# SumoDuino.net
KiCad netlist of a schematic drawn in EAGLE
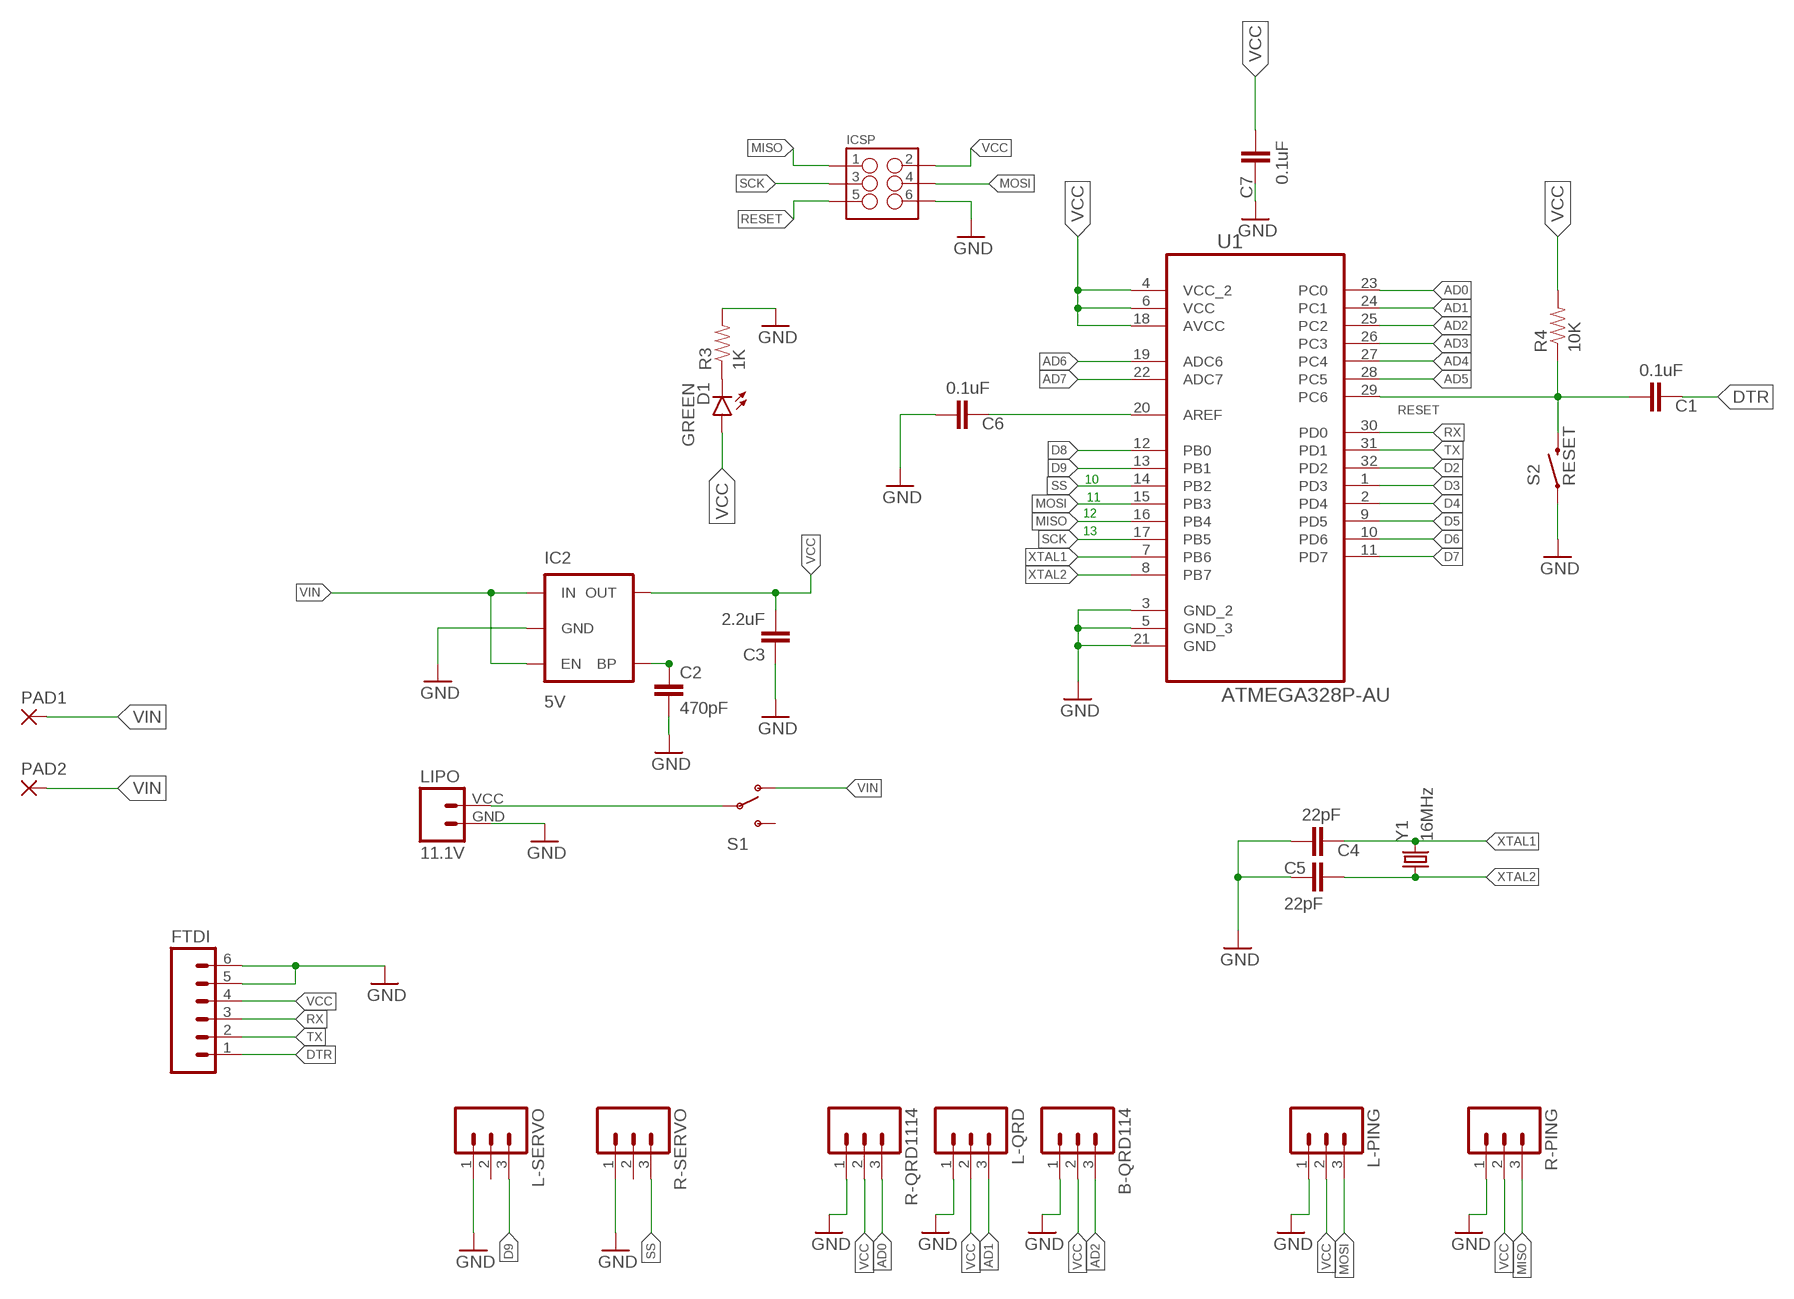
[diagram p0: schematic, sheet 1]

(export (version "E")
  (design (tool "Eeschema 10.0.6"))
  (components
    (comp (ref "B-QRD114")
      (value "M03PTH")
      (footprint "eagle-import:1X03")
      (libsource (lib "eagle-import") (part "M03PTH"))
    )
    (comp (ref "C1")
      (value "0.1uF")
      (footprint "eagle-import:0603-CAP")
      (libsource (lib "eagle-import") (part "CAP0603-CAP"))
    )
    (comp (ref "C2")
      (value "470pF")
      (footprint "eagle-import:0603-CAP")
      (libsource (lib "eagle-import") (part "CAP0603-CAP"))
    )
    (comp (ref "C3")
      (value "2.2uF")
      (footprint "eagle-import:0603-CAP")
      (libsource (lib "eagle-import") (part "CAP0603-CAP"))
    )
    (comp (ref "C4")
      (value "22pF")
      (footprint "eagle-import:0603-CAP")
      (libsource (lib "eagle-import") (part "CAP0603-CAP"))
    )
    (comp (ref "C5")
      (value "22pF")
      (footprint "eagle-import:0603-CAP")
      (libsource (lib "eagle-import") (part "CAP0603-CAP"))
    )
    (comp (ref "C6")
      (value "0.1uF")
      (footprint "eagle-import:0603-CAP")
      (libsource (lib "eagle-import") (part "CAP0603-CAP"))
    )
    (comp (ref "C7")
      (value "0.1uF")
      (footprint "eagle-import:0603-CAP")
      (libsource (lib "eagle-import") (part "CAP0603-CAP"))
    )
    (comp (ref "D1")
      (value "GREEN")
      (footprint "eagle-import:LED-0603")
      (libsource (lib "eagle-import") (part "LED-GREEN0603"))
    )
    (comp (ref "FTDI")
      (value "M06LOCK")
      (footprint "eagle-import:1X06_LOCK")
      (libsource (lib "eagle-import") (part "M06LOCK"))
    )
    (comp (ref "IC2")
      (value "5V")
      (footprint "eagle-import:SOT23-5")
      (libsource (lib "eagle-import") (part "V_REG_MIC52055V"))
    )
    (comp (ref "ICSP")
      (value "M03X22X3_SILK_MALE_PTH")
      (footprint "eagle-import:2X3")
      (libsource (lib "eagle-import") (part "M03X22X3_SILK_MALE_PTH"))
    )
    (comp (ref "L-PING")
      (value "M03PTH")
      (footprint "eagle-import:1X03")
      (libsource (lib "eagle-import") (part "M03PTH"))
    )
    (comp (ref "L-QRD")
      (value "M03PTH")
      (footprint "eagle-import:1X03")
      (libsource (lib "eagle-import") (part "M03PTH"))
    )
    (comp (ref "L-SERVO")
      (value "M03PTH")
      (footprint "eagle-import:1X03")
      (libsource (lib "eagle-import") (part "M03PTH"))
    )
    (comp (ref "LIPO")
      (value "11.1V")
      (footprint "eagle-import:JST-2-SMD-VERT")
      (libsource (lib "eagle-import") (part "M024UCON-15767"))
    )
    (comp (ref "PAD1")
      (value "1,6/0,8")
      (footprint "eagle-import:1,6_0,8")
      (libsource (lib "eagle-import") (part "1,6/0,8"))
    )
    (comp (ref "PAD2")
      (value "1,6/0,8")
      (footprint "eagle-import:1,6_0,8")
      (libsource (lib "eagle-import") (part "1,6/0,8"))
    )
    (comp (ref "R-PING")
      (value "M03PTH")
      (footprint "eagle-import:1X03")
      (libsource (lib "eagle-import") (part "M03PTH"))
    )
    (comp (ref "R-QRD1114")
      (value "M03PTH")
      (footprint "eagle-import:1X03")
      (libsource (lib "eagle-import") (part "M03PTH"))
    )
    (comp (ref "R-SERVO")
      (value "M03PTH")
      (footprint "eagle-import:1X03")
      (libsource (lib "eagle-import") (part "M03PTH"))
    )
    (comp (ref "R3")
      (value "1K")
      (footprint "eagle-import:0603-RES")
      (libsource (lib "eagle-import") (part "RESISTOR0603"))
    )
    (comp (ref "R4")
      (value "10K")
      (footprint "eagle-import:0603-RES")
      (libsource (lib "eagle-import") (part "RESISTOR0603"))
    )
    (comp (ref "S1")
      (value "SWITCH-SPDTPTH")
      (footprint "eagle-import:SWITCH-SPDT")
      (libsource (lib "eagle-import") (part "SWITCH-SPDTPTH"))
    )
    (comp (ref "S2")
      (value "RESET")
      (footprint "eagle-import:TACTILE-PTH")
      (libsource (lib "eagle-import") (part "SWITCH-MOMENTARY-2PTH"))
    )
    (comp (ref "U1")
      (value "ATMEGA328P-AU")
      (footprint "eagle-import:QFP80P900X900X120-32N")
      (libsource (lib "eagle-import") (part "ATMEGA328P-AU"))
    )
    (comp (ref "Y1")
      (value "16MHz")
      (footprint "eagle-import:HC49US")
      (libsource (lib "eagle-import") (part "CRYSTALHC49US"))
    )
  )
  (nets
    (net (code "1") (name "AD0") (class "Default")
      (node (ref "R-QRD1114") (pin "3") (pinfunction "3_3") (pintype "passive"))
      (node (ref "U1") (pin "23") (pinfunction "PC0_23") (pintype "bidirectional"))
    )
    (net (code "2") (name "AD1") (class "Default")
      (node (ref "L-QRD") (pin "3") (pinfunction "3_3") (pintype "passive"))
      (node (ref "U1") (pin "24") (pinfunction "PC1_24") (pintype "bidirectional"))
    )
    (net (code "3") (name "AD2") (class "Default")
      (node (ref "B-QRD114") (pin "3") (pinfunction "3_3") (pintype "passive"))
      (node (ref "U1") (pin "25") (pinfunction "PC2_25") (pintype "bidirectional"))
    )
    (net (code "4") (name "AD3") (class "Default")
      (node (ref "U1") (pin "26") (pinfunction "PC3_26") (pintype "bidirectional"))
    )
    (net (code "5") (name "AD4") (class "Default")
      (node (ref "U1") (pin "27") (pinfunction "PC4_27") (pintype "bidirectional"))
    )
    (net (code "6") (name "AD5") (class "Default")
      (node (ref "U1") (pin "28") (pinfunction "PC5_28") (pintype "bidirectional"))
    )
    (net (code "7") (name "AD6") (class "Default")
      (node (ref "U1") (pin "19") (pinfunction "ADC6_19") (pintype "input"))
    )
    (net (code "8") (name "AD7") (class "Default")
      (node (ref "U1") (pin "22") (pinfunction "ADC7_22") (pintype "input"))
    )
    (net (code "9") (name "D2") (class "Default")
      (node (ref "U1") (pin "32") (pinfunction "PD2_32") (pintype "bidirectional"))
    )
    (net (code "10") (name "D3") (class "Default")
      (node (ref "U1") (pin "1") (pinfunction "PD3_1") (pintype "bidirectional"))
    )
    (net (code "11") (name "D4") (class "Default")
      (node (ref "U1") (pin "2") (pinfunction "PD4_2") (pintype "bidirectional"))
    )
    (net (code "12") (name "D5") (class "Default")
      (node (ref "U1") (pin "9") (pinfunction "PD5_9") (pintype "bidirectional"))
    )
    (net (code "13") (name "D6") (class "Default")
      (node (ref "U1") (pin "10") (pinfunction "PD6_10") (pintype "bidirectional"))
    )
    (net (code "14") (name "D7") (class "Default")
      (node (ref "U1") (pin "11") (pinfunction "PD7_11") (pintype "bidirectional"))
    )
    (net (code "15") (name "D8") (class "Default")
      (node (ref "U1") (pin "12") (pinfunction "PB0_12") (pintype "bidirectional"))
    )
    (net (code "16") (name "D9") (class "Default")
      (node (ref "L-SERVO") (pin "3") (pinfunction "3_3") (pintype "passive"))
      (node (ref "U1") (pin "13") (pinfunction "PB1_13") (pintype "bidirectional"))
    )
    (net (code "17") (name "DTR") (class "Default")
      (node (ref "C1") (pin "1") (pinfunction "1_1") (pintype "passive"))
      (node (ref "FTDI") (pin "1") (pinfunction "1_1") (pintype "passive"))
    )
    (net (code "18") (name "GND") (class "Default")
      (node (ref "B-QRD114") (pin "1") (pinfunction "1_1") (pintype "passive"))
      (node (ref "C2") (pin "2") (pinfunction "2_2") (pintype "passive"))
      (node (ref "C3") (pin "1") (pinfunction "1_1") (pintype "passive"))
      (node (ref "C4") (pin "2") (pinfunction "2_2") (pintype "passive"))
      (node (ref "C5") (pin "2") (pinfunction "2_2") (pintype "passive"))
      (node (ref "C6") (pin "2") (pinfunction "2_2") (pintype "passive"))
      (node (ref "C7") (pin "1") (pinfunction "1_1") (pintype "passive"))
      (node (ref "FTDI") (pin "5") (pinfunction "5_5") (pintype "passive"))
      (node (ref "FTDI") (pin "6") (pinfunction "6_6") (pintype "passive"))
      (node (ref "IC2") (pin "2") (pinfunction "GND_2") (pintype "input"))
      (node (ref "ICSP") (pin "6") (pinfunction "6_6") (pintype "bidirectional"))
      (node (ref "L-PING") (pin "1") (pinfunction "1_1") (pintype "passive"))
      (node (ref "L-QRD") (pin "1") (pinfunction "1_1") (pintype "passive"))
      (node (ref "L-SERVO") (pin "1") (pinfunction "1_1") (pintype "passive"))
      (node (ref "LIPO") (pin "GND") (pinfunction "1_GND") (pintype "passive"))
      (node (ref "R-PING") (pin "1") (pinfunction "1_1") (pintype "passive"))
      (node (ref "R-QRD1114") (pin "1") (pinfunction "1_1") (pintype "passive"))
      (node (ref "R-SERVO") (pin "1") (pinfunction "1_1") (pintype "passive"))
      (node (ref "R3") (pin "2") (pinfunction "2_2") (pintype "passive"))
      (node (ref "S2") (pin "1") (pinfunction "1_1") (pintype "passive"))
      (node (ref "U1") (pin "21") (pinfunction "GND_21") (pintype "passive"))
      (node (ref "U1") (pin "3") (pinfunction "GND_2_3") (pintype "passive"))
      (node (ref "U1") (pin "5") (pinfunction "GND_3_5") (pintype "passive"))
    )
    (net (code "19") (name "MISO") (class "Default")
      (node (ref "ICSP") (pin "1") (pinfunction "1_1") (pintype "bidirectional"))
      (node (ref "R-PING") (pin "3") (pinfunction "3_3") (pintype "passive"))
      (node (ref "U1") (pin "16") (pinfunction "PB4_16") (pintype "bidirectional"))
    )
    (net (code "20") (name "MOSI") (class "Default")
      (node (ref "ICSP") (pin "4") (pinfunction "4_4") (pintype "bidirectional"))
      (node (ref "L-PING") (pin "3") (pinfunction "3_3") (pintype "passive"))
      (node (ref "U1") (pin "15") (pinfunction "PB3_15") (pintype "bidirectional"))
    )
    (net (code "21") (name "Net-(D1-PadC)") (class "Default")
      (node (ref "D1") (pin "C") (pinfunction "C_C") (pintype "passive"))
      (node (ref "R3") (pin "1") (pinfunction "1_1") (pintype "passive"))
    )
    (net (code "22") (name "Net-(IC2-BP)") (class "Default")
      (node (ref "C2") (pin "1") (pinfunction "1_1") (pintype "passive"))
      (node (ref "IC2") (pin "4") (pinfunction "BP_4") (pintype "input"))
    )
    (net (code "23") (name "Net-(LIPO-2)") (class "Default")
      (node (ref "LIPO") (pin "VCC") (pinfunction "2_VCC") (pintype "passive"))
      (node (ref "S1") (pin "2") (pinfunction "P_2") (pintype "passive"))
    )
    (net (code "24") (name "Net-(U1-AREF)") (class "Default")
      (node (ref "C6") (pin "1") (pinfunction "1_1") (pintype "passive"))
      (node (ref "U1") (pin "20") (pinfunction "AREF_20") (pintype "input"))
    )
    (net (code "25") (name "RESET") (class "Default")
      (node (ref "C1") (pin "2") (pinfunction "2_2") (pintype "passive"))
      (node (ref "ICSP") (pin "5") (pinfunction "5_5") (pintype "bidirectional"))
      (node (ref "R4") (pin "1") (pinfunction "1_1") (pintype "passive"))
      (node (ref "S2") (pin "3") (pinfunction "2_3") (pintype "passive"))
      (node (ref "U1") (pin "29") (pinfunction "PC6_29") (pintype "bidirectional"))
    )
    (net (code "26") (name "RX") (class "Default")
      (node (ref "FTDI") (pin "3") (pinfunction "3_3") (pintype "passive"))
      (node (ref "U1") (pin "30") (pinfunction "PD0_30") (pintype "bidirectional"))
    )
    (net (code "27") (name "SCK") (class "Default")
      (node (ref "ICSP") (pin "3") (pinfunction "3_3") (pintype "bidirectional"))
      (node (ref "U1") (pin "17") (pinfunction "PB5_17") (pintype "bidirectional"))
    )
    (net (code "28") (name "SS") (class "Default")
      (node (ref "R-SERVO") (pin "3") (pinfunction "3_3") (pintype "passive"))
      (node (ref "U1") (pin "14") (pinfunction "PB2_14") (pintype "bidirectional"))
    )
    (net (code "29") (name "TX") (class "Default")
      (node (ref "FTDI") (pin "2") (pinfunction "2_2") (pintype "passive"))
      (node (ref "U1") (pin "31") (pinfunction "PD1_31") (pintype "bidirectional"))
    )
    (net (code "30") (name "VCC") (class "Default")
      (node (ref "B-QRD114") (pin "2") (pinfunction "2_2") (pintype "passive"))
      (node (ref "C3") (pin "2") (pinfunction "2_2") (pintype "passive"))
      (node (ref "C7") (pin "2") (pinfunction "2_2") (pintype "passive"))
      (node (ref "D1") (pin "A") (pinfunction "A_A") (pintype "passive"))
      (node (ref "FTDI") (pin "4") (pinfunction "4_4") (pintype "passive"))
      (node (ref "IC2") (pin "5") (pinfunction "OUT_5") (pintype "passive"))
      (node (ref "ICSP") (pin "2") (pinfunction "2_2") (pintype "bidirectional"))
      (node (ref "L-PING") (pin "2") (pinfunction "2_2") (pintype "passive"))
      (node (ref "L-QRD") (pin "2") (pinfunction "2_2") (pintype "passive"))
      (node (ref "R-PING") (pin "2") (pinfunction "2_2") (pintype "passive"))
      (node (ref "R-QRD1114") (pin "2") (pinfunction "2_2") (pintype "passive"))
      (node (ref "R4") (pin "2") (pinfunction "2_2") (pintype "passive"))
      (node (ref "U1") (pin "18") (pinfunction "AVCC_18") (pintype "power_in"))
      (node (ref "U1") (pin "4") (pinfunction "VCC_2_4") (pintype "power_in"))
      (node (ref "U1") (pin "6") (pinfunction "VCC_6") (pintype "power_in"))
    )
    (net (code "31") (name "VIN") (class "Default")
      (node (ref "IC2") (pin "1") (pinfunction "IN_1") (pintype "input"))
      (node (ref "IC2") (pin "3") (pinfunction "EN_3") (pintype "input"))
      (node (ref "PAD1") (pin "1") (pinfunction "P_1") (pintype "passive"))
      (node (ref "PAD2") (pin "1") (pinfunction "P_1") (pintype "passive"))
      (node (ref "S1") (pin "1") (pinfunction "O_1") (pintype "passive"))
    )
    (net (code "32") (name "XTAL1") (class "Default")
      (node (ref "C4") (pin "1") (pinfunction "1_1") (pintype "passive"))
      (node (ref "U1") (pin "7") (pinfunction "PB6_7") (pintype "bidirectional"))
      (node (ref "Y1") (pin "2") (pinfunction "2_2") (pintype "passive"))
    )
    (net (code "33") (name "XTAL2") (class "Default")
      (node (ref "C5") (pin "1") (pinfunction "1_1") (pintype "passive"))
      (node (ref "U1") (pin "8") (pinfunction "PB7_8") (pintype "bidirectional"))
      (node (ref "Y1") (pin "1") (pinfunction "1_1") (pintype "passive"))
    )
    (net (code "34") (name "unconnected-(L-SERVO-Pad2)") (class "Default")
      (node (ref "L-SERVO") (pin "2") (pinfunction "2_2") (pintype "passive"))
    )
    (net (code "35") (name "unconnected-(R-SERVO-Pad2)") (class "Default")
      (node (ref "R-SERVO") (pin "2") (pinfunction "2_2") (pintype "passive"))
    )
    (net (code "36") (name "unconnected-(S1-S-Pad3)") (class "Default")
      (node (ref "S1") (pin "3") (pinfunction "S_3") (pintype "passive"))
    )
  )
)
